# Radii.net
KiCad netlist of a schematic drawn in EAGLE
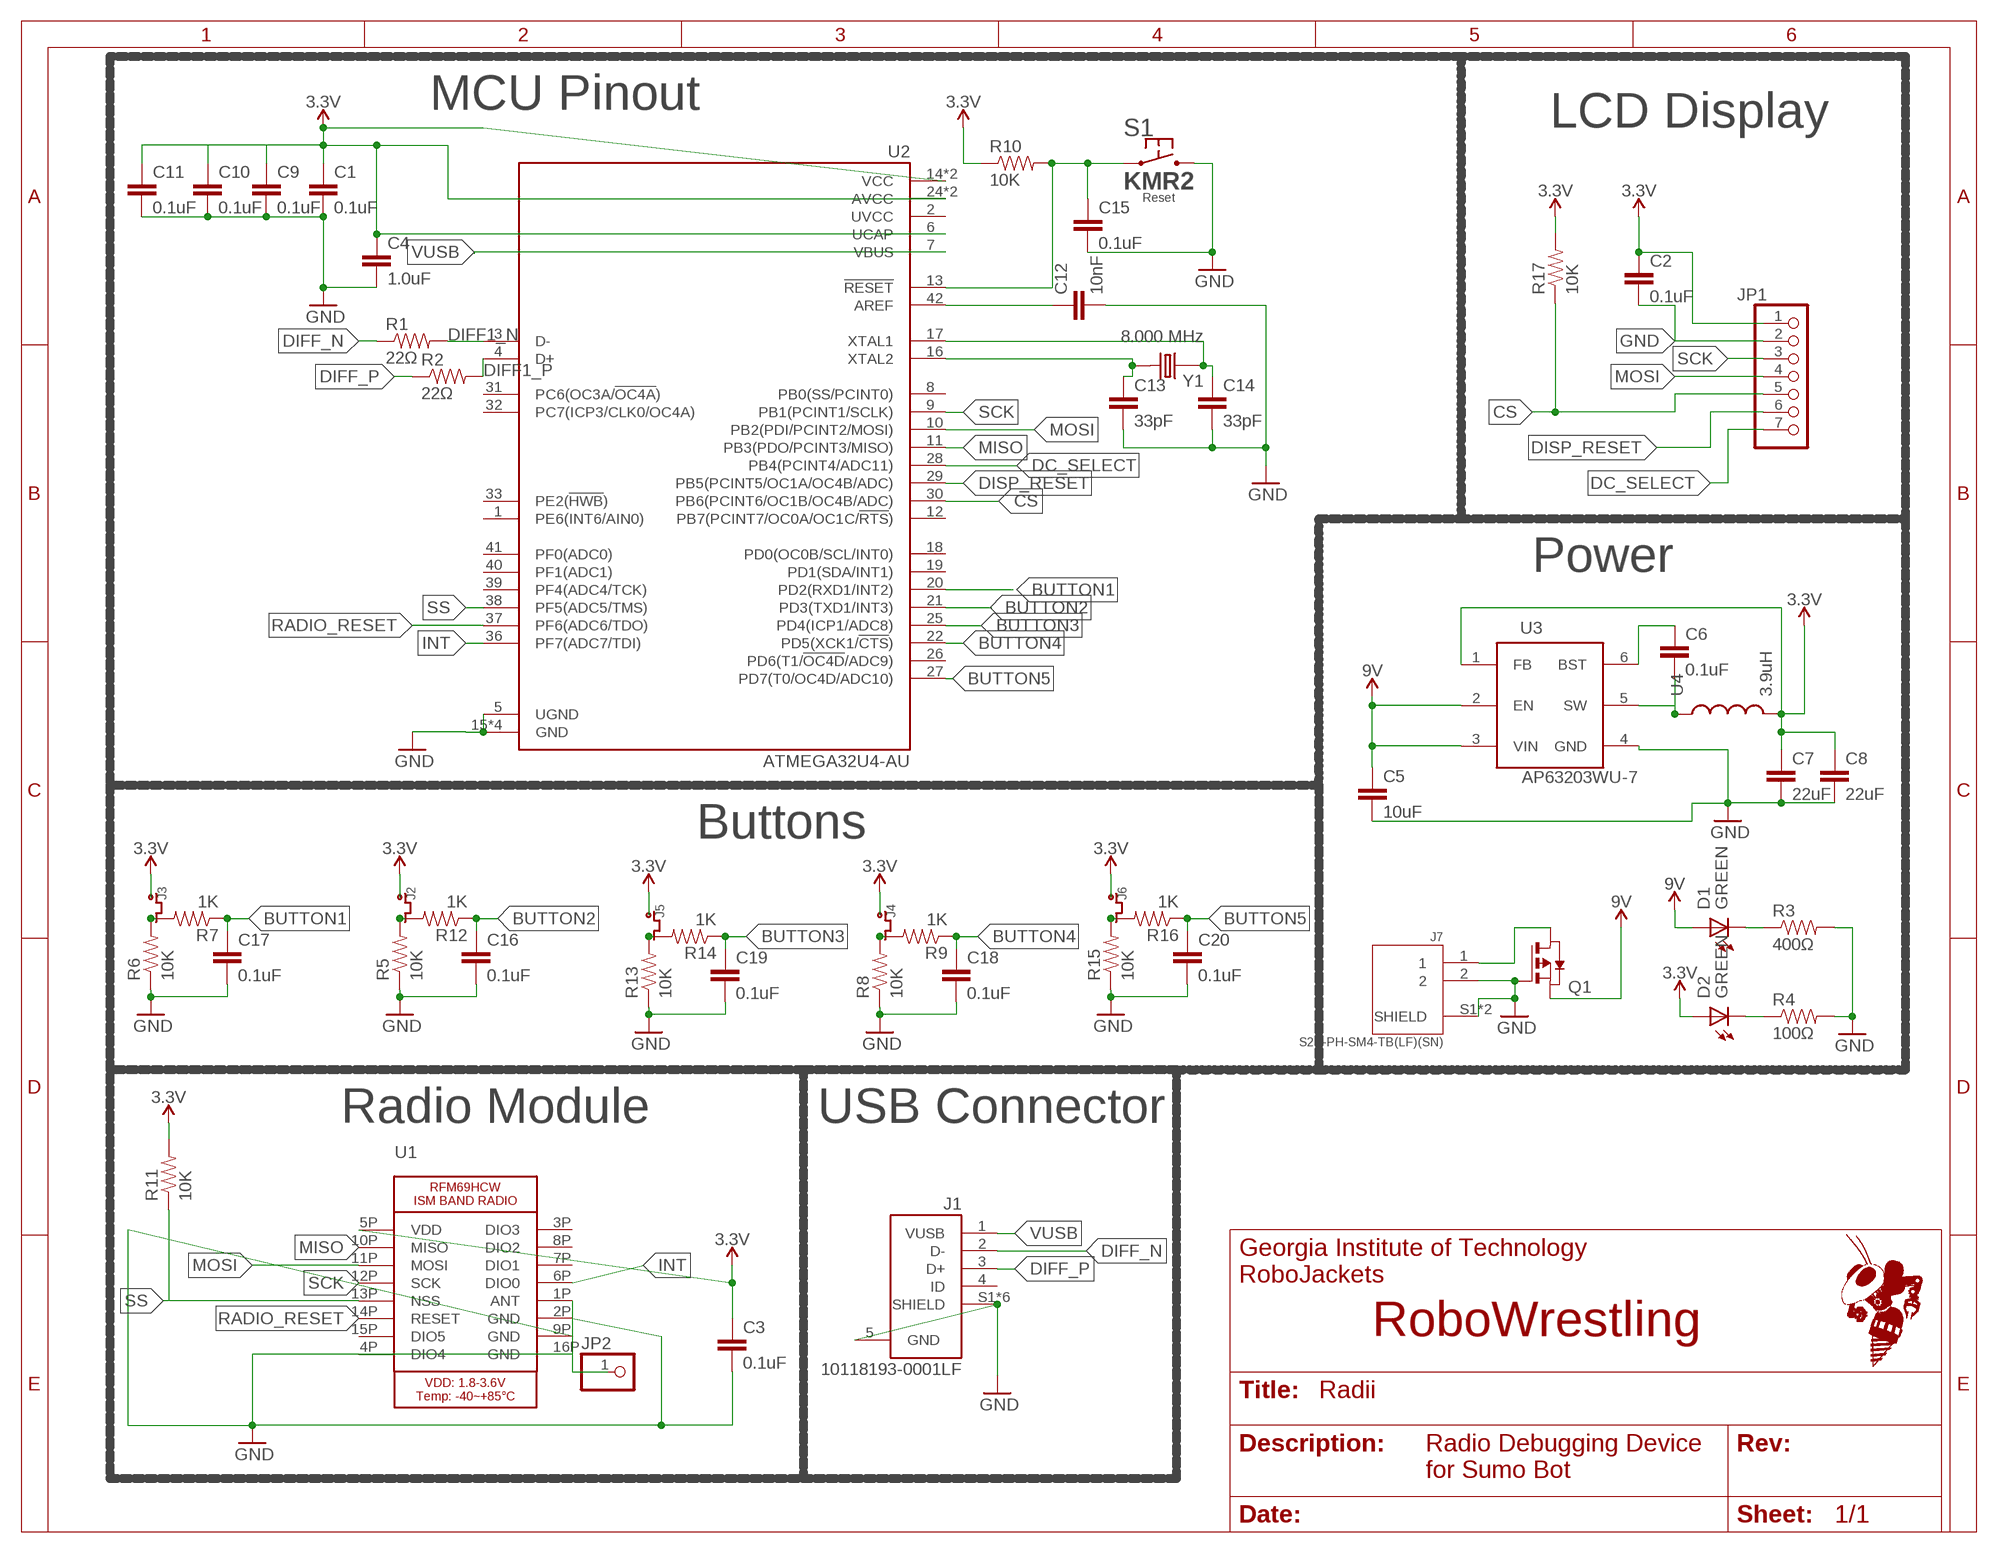
[diagram p0: schematic, sheet 1]

(export (version "E")
  (design (tool "Eeschema 10.0.6"))
  (components
    (comp (ref "C1")
      (value "0.1uF")
      (footprint "eagle-import:0603")
      (libsource (lib "eagle-import") (part "0.1UF-0603-25V-(+80/-20%)"))
    )
    (comp (ref "C2")
      (value "0.1uF")
      (footprint "eagle-import:0603")
      (libsource (lib "eagle-import") (part "0.1UF-0603-25V-(+80/-20%)"))
    )
    (comp (ref "C3")
      (value "0.1uF")
      (footprint "eagle-import:0603")
      (libsource (lib "eagle-import") (part "0.1UF-0603-25V-(+80/-20%)"))
    )
    (comp (ref "C4")
      (value "1.0uF")
      (footprint "eagle-import:0603")
      (libsource (lib "eagle-import") (part "1.0UF-0603-16V-10%"))
    )
    (comp (ref "C5")
      (value "10uF")
      (footprint "eagle-import:0603")
      (libsource (lib "eagle-import") (part "10UF-0603-6.3V-20%"))
    )
    (comp (ref "C6")
      (value "0.1uF")
      (footprint "eagle-import:0603")
      (libsource (lib "eagle-import") (part "0.1UF-0603-25V-(+80/-20%)"))
    )
    (comp (ref "C7")
      (value "22uF")
      (footprint "eagle-import:1210")
      (libsource (lib "eagle-import") (part "22UF-1210-16V-20%"))
    )
    (comp (ref "C8")
      (value "22uF")
      (footprint "eagle-import:1210")
      (libsource (lib "eagle-import") (part "22UF-1210-16V-20%"))
    )
    (comp (ref "C9")
      (value "0.1uF")
      (footprint "eagle-import:0603")
      (libsource (lib "eagle-import") (part "0.1UF-0603-25V-(+80/-20%)"))
    )
    (comp (ref "C10")
      (value "0.1uF")
      (footprint "eagle-import:0603")
      (libsource (lib "eagle-import") (part "0.1UF-0603-25V-(+80/-20%)"))
    )
    (comp (ref "C11")
      (value "0.1uF")
      (footprint "eagle-import:0603")
      (libsource (lib "eagle-import") (part "0.1UF-0603-25V-(+80/-20%)"))
    )
    (comp (ref "C12")
      (value "10nF")
      (footprint "eagle-import:0603")
      (libsource (lib "eagle-import") (part "10NF-0603-50V-10%"))
    )
    (comp (ref "C13")
      (value "33pF")
      (footprint "eagle-import:0603")
      (libsource (lib "eagle-import") (part "33PF-0603-50V-5%"))
    )
    (comp (ref "C14")
      (value "33pF")
      (footprint "eagle-import:0603")
      (libsource (lib "eagle-import") (part "33PF-0603-50V-5%"))
    )
    (comp (ref "C15")
      (value "0.1uF")
      (footprint "eagle-import:0603")
      (libsource (lib "eagle-import") (part "0.1UF-0603-25V-(+80/-20%)"))
    )
    (comp (ref "C16")
      (value "0.1uF")
      (footprint "eagle-import:0603")
      (libsource (lib "eagle-import") (part "0.1UF-0603-25V-(+80/-20%)"))
    )
    (comp (ref "C17")
      (value "0.1uF")
      (footprint "eagle-import:0603")
      (libsource (lib "eagle-import") (part "0.1UF-0603-25V-(+80/-20%)"))
    )
    (comp (ref "C18")
      (value "0.1uF")
      (footprint "eagle-import:0603")
      (libsource (lib "eagle-import") (part "0.1UF-0603-25V-(+80/-20%)"))
    )
    (comp (ref "C19")
      (value "0.1uF")
      (footprint "eagle-import:0603")
      (libsource (lib "eagle-import") (part "0.1UF-0603-25V-(+80/-20%)"))
    )
    (comp (ref "C20")
      (value "0.1uF")
      (footprint "eagle-import:0603")
      (libsource (lib "eagle-import") (part "0.1UF-0603-25V-(+80/-20%)"))
    )
    (comp (ref "D1")
      (value "GREEN")
      (footprint "eagle-import:CHIP-LED0603")
      (libsource (lib "eagle-import") (part "LED-SMD"))
    )
    (comp (ref "D2")
      (value "GREEN")
      (footprint "eagle-import:CHIP-LED0603")
      (libsource (lib "eagle-import") (part "LED-SMD"))
    )
    (comp (ref "J1")
      (value "10118193-0001LF")
      (footprint "eagle-import:FCI_10118193-0001LF")
      (libsource (lib "eagle-import") (part "10118193-0001LF"))
    )
    (comp (ref "J2")
      (value "BUTTON")
      (footprint "eagle-import:1X02")
      (libsource (lib "eagle-import") (part "BUTTON"))
    )
    (comp (ref "J3")
      (value "BUTTON")
      (footprint "eagle-import:1X02")
      (libsource (lib "eagle-import") (part "BUTTON"))
    )
    (comp (ref "J4")
      (value "BUTTON")
      (footprint "eagle-import:1X02")
      (libsource (lib "eagle-import") (part "BUTTON"))
    )
    (comp (ref "J5")
      (value "BUTTON")
      (footprint "eagle-import:1X02")
      (libsource (lib "eagle-import") (part "BUTTON"))
    )
    (comp (ref "J6")
      (value "BUTTON")
      (footprint "eagle-import:1X02")
      (libsource (lib "eagle-import") (part "BUTTON"))
    )
    (comp (ref "J7")
      (value "S2B-PH-SM4-TB(LF)(SN)")
      (footprint "eagle-import:JST_S2B-PH-SM4-TB(LF)(SN)")
      (fields (field (name "DIGI-KEY_PART_NUMBER") "455-1749-1-ND"))
      (libsource (lib "eagle-import") (part "S2B-PH-SM4-TB(LF)(SN)"))
    )
    (comp (ref "JP1")
      (value "PINHD-1X7")
      (footprint "eagle-import:1X07")
      (libsource (lib "eagle-import") (part "PINHD-1X7"))
    )
    (comp (ref "JP2")
      (value "PINHD-1X1")
      (footprint "eagle-import:1X01")
      (libsource (lib "eagle-import") (part "PINHD-1X1"))
    )
    (comp (ref "Q1")
      (value "PMOS")
      (footprint "eagle-import:SOT-23-3")
      (libsource (lib "eagle-import") (part "PMOS"))
    )
    (comp (ref "R1")
      (value "22Ω")
      (footprint "eagle-import:0603-RES")
      (libsource (lib "eagle-import") (part "22OHM1/10W1%(0603)"))
    )
    (comp (ref "R2")
      (value "22Ω")
      (footprint "eagle-import:0603-RES")
      (libsource (lib "eagle-import") (part "22OHM1/10W1%(0603)"))
    )
    (comp (ref "R3")
      (value "400Ω")
      (footprint "eagle-import:0603-RES")
      (libsource (lib "eagle-import") (part "RESISTOR0603"))
    )
    (comp (ref "R4")
      (value "100Ω")
      (footprint "eagle-import:0603-RES")
      (libsource (lib "eagle-import") (part "RESISTOR0603"))
    )
    (comp (ref "R5")
      (value "10K")
      (footprint "eagle-import:0603-RES")
      (libsource (lib "eagle-import") (part "10KOHM-1/10W-1%(0603)0603"))
    )
    (comp (ref "R6")
      (value "10K")
      (footprint "eagle-import:0603-RES")
      (libsource (lib "eagle-import") (part "10KOHM-1/10W-1%(0603)0603"))
    )
    (comp (ref "R7")
      (value "1K")
      (footprint "eagle-import:0603-RES")
      (libsource (lib "eagle-import") (part "10KOHM-1/10W-1%(0603)0603"))
    )
    (comp (ref "R8")
      (value "10K")
      (footprint "eagle-import:0603-RES")
      (libsource (lib "eagle-import") (part "10KOHM-1/10W-1%(0603)0603"))
    )
    (comp (ref "R9")
      (value "1K")
      (footprint "eagle-import:0603-RES")
      (libsource (lib "eagle-import") (part "10KOHM-1/10W-1%(0603)0603"))
    )
    (comp (ref "R10")
      (value "10K")
      (footprint "eagle-import:0603-RES")
      (libsource (lib "eagle-import") (part "10KOHM-1/10W-1%(0603)0603"))
    )
    (comp (ref "R11")
      (value "10K")
      (footprint "eagle-import:0603-RES")
      (libsource (lib "eagle-import") (part "10KOHM-1/10W-1%(0603)0603"))
    )
    (comp (ref "R12")
      (value "1K")
      (footprint "eagle-import:0603-RES")
      (libsource (lib "eagle-import") (part "10KOHM-1/10W-1%(0603)0603"))
    )
    (comp (ref "R13")
      (value "10K")
      (footprint "eagle-import:0603-RES")
      (libsource (lib "eagle-import") (part "10KOHM-1/10W-1%(0603)0603"))
    )
    (comp (ref "R14")
      (value "1K")
      (footprint "eagle-import:0603-RES")
      (libsource (lib "eagle-import") (part "10KOHM-1/10W-1%(0603)0603"))
    )
    (comp (ref "R15")
      (value "10K")
      (footprint "eagle-import:0603-RES")
      (libsource (lib "eagle-import") (part "10KOHM-1/10W-1%(0603)0603"))
    )
    (comp (ref "R16")
      (value "1K")
      (footprint "eagle-import:0603-RES")
      (libsource (lib "eagle-import") (part "10KOHM-1/10W-1%(0603)0603"))
    )
    (comp (ref "R17")
      (value "10K")
      (footprint "eagle-import:0603-RES")
      (libsource (lib "eagle-import") (part "10KOHM-1/10W-1%(0603)0603"))
    )
    (comp (ref "S1")
      (value "KMR2")
      (footprint "eagle-import:KMR2")
      (fields (field (name "FUNCTION") "Reset"))
      (libsource (lib "eagle-import") (part "KMR2"))
    )
    (comp (ref "U1")
      (value "RFM69HCW_SMT")
      (footprint "eagle-import:RFMHCW_SMT")
      (libsource (lib "eagle-import") (part "RFM69HCW_SMT"))
    )
    (comp (ref "U2")
      (value "ATMEGA32U4-AU")
      (footprint "eagle-import:44-TQFP(10X10)")
      (libsource (lib "eagle-import") (part "ATMEGA32U4-AUR"))
    )
    (comp (ref "U3")
      (value "AP63203WU-7")
      (footprint "eagle-import:TSOT-23-6")
      (libsource (lib "eagle-import") (part "AP63203WU-7"))
    )
    (comp (ref "U4")
      (value "3.9uH")
      (footprint "eagle-import:1255AY-3R9N=P3")
      (fields (field (name "TOLERANCE") "±30%"))
      (libsource (lib "eagle-import") (part "1255AY-3R9N=P3"))
    )
    (comp (ref "Y1")
      (value "8.000 MHz")
      (footprint "eagle-import:XTAL_ECS-80-20-5PX-TR")
      (libsource (lib "eagle-import") (part "ECS-80-20-5PX-TR"))
    )
  )
  (nets
    (net (code "1") (name "/DIFF1_N") (class "Default")
      (node (ref "R1") (pin "2") (pinfunction "2_2") (pintype "passive"))
      (node (ref "U2") (pin "3") (pinfunction "D-_3") (pintype "passive"))
    )
    (net (code "2") (name "/DIFF1_P") (class "Default")
      (node (ref "R2") (pin "2") (pinfunction "2_2") (pintype "passive"))
      (node (ref "U2") (pin "4") (pinfunction "D+_4") (pintype "passive"))
    )
    (net (code "3") (name "3.3V") (class "Default")
      (node (ref "C1") (pin "1") (pinfunction "1_1") (pintype "passive"))
      (node (ref "C10") (pin "1") (pinfunction "1_1") (pintype "passive"))
      (node (ref "C11") (pin "1") (pinfunction "1_1") (pintype "passive"))
      (node (ref "C2") (pin "1") (pinfunction "1_1") (pintype "passive"))
      (node (ref "C3") (pin "1") (pinfunction "1_1") (pintype "passive"))
      (node (ref "C4") (pin "1") (pinfunction "1_1") (pintype "passive"))
      (node (ref "C7") (pin "1") (pinfunction "1_1") (pintype "passive"))
      (node (ref "C8") (pin "1") (pinfunction "1_1") (pintype "passive"))
      (node (ref "C9") (pin "1") (pinfunction "1_1") (pintype "passive"))
      (node (ref "D2") (pin "A") (pinfunction "A_A") (pintype "passive"))
      (node (ref "J2") (pin "1") (pinfunction "P$1_1") (pintype "passive"))
      (node (ref "J3") (pin "1") (pinfunction "P$1_1") (pintype "passive"))
      (node (ref "J4") (pin "1") (pinfunction "P$1_1") (pintype "passive"))
      (node (ref "J5") (pin "1") (pinfunction "P$1_1") (pintype "passive"))
      (node (ref "J6") (pin "1") (pinfunction "P$1_1") (pintype "passive"))
      (node (ref "JP1") (pin "1") (pinfunction "1_1") (pintype "passive"))
      (node (ref "R10") (pin "1") (pinfunction "1_1") (pintype "passive"))
      (node (ref "R11") (pin "2") (pinfunction "2_2") (pintype "passive"))
      (node (ref "R17") (pin "2") (pinfunction "2_2") (pintype "passive"))
      (node (ref "U1") (pin "5P") (pinfunction "VDD_5P") (pintype "passive"))
      (node (ref "U2") (pin "14") (pinfunction "VCC_14") (pintype "passive"))
      (node (ref "U2") (pin "24") (pinfunction "AVCC_24") (pintype "passive"))
      (node (ref "U2") (pin "34") (pinfunction "VCC_34") (pintype "passive"))
      (node (ref "U2") (pin "44") (pinfunction "AVCC_44") (pintype "passive"))
      (node (ref "U2") (pin "6") (pinfunction "UCAP_6") (pintype "passive"))
      (node (ref "U3") (pin "1") (pinfunction "FB_1") (pintype "passive"))
      (node (ref "U4") (pin "2") (pinfunction "2_2") (pintype "passive"))
    )
    (net (code "4") (name "9V") (class "Default")
      (node (ref "C5") (pin "1") (pinfunction "1_1") (pintype "passive"))
      (node (ref "D1") (pin "A") (pinfunction "A_A") (pintype "passive"))
      (node (ref "Q1") (pin "2") (pinfunction "S_2") (pintype "passive"))
      (node (ref "U3") (pin "2") (pinfunction "EN_2") (pintype "passive"))
      (node (ref "U3") (pin "3") (pinfunction "VIN_3") (pintype "passive"))
    )
    (net (code "5") (name "BUTTON1") (class "Default")
      (node (ref "C17") (pin "1") (pinfunction "1_1") (pintype "passive"))
      (node (ref "R7") (pin "1") (pinfunction "1_1") (pintype "passive"))
      (node (ref "U2") (pin "20") (pinfunction "PD2(RXD1/INT2)_20") (pintype "passive"))
    )
    (net (code "6") (name "BUTTON2") (class "Default")
      (node (ref "C16") (pin "1") (pinfunction "1_1") (pintype "passive"))
      (node (ref "R12") (pin "1") (pinfunction "1_1") (pintype "passive"))
      (node (ref "U2") (pin "21") (pinfunction "PD3(TXD1/INT3)_21") (pintype "passive"))
    )
    (net (code "7") (name "BUTTON3") (class "Default")
      (node (ref "C19") (pin "1") (pinfunction "1_1") (pintype "passive"))
      (node (ref "R14") (pin "1") (pinfunction "1_1") (pintype "passive"))
      (node (ref "U2") (pin "25") (pinfunction "PD4(ICP1/ADC8)_25") (pintype "passive"))
    )
    (net (code "8") (name "BUTTON4") (class "Default")
      (node (ref "C18") (pin "1") (pinfunction "1_1") (pintype "passive"))
      (node (ref "R9") (pin "1") (pinfunction "1_1") (pintype "passive"))
      (node (ref "U2") (pin "22") (pinfunction "PD5(XCK1/~{CTS})_22") (pintype "passive"))
    )
    (net (code "9") (name "BUTTON5") (class "Default")
      (node (ref "C20") (pin "1") (pinfunction "1_1") (pintype "passive"))
      (node (ref "R16") (pin "1") (pinfunction "1_1") (pintype "passive"))
      (node (ref "U2") (pin "27") (pinfunction "PD7(T0/OC4D/ADC10)_27") (pintype "passive"))
    )
    (net (code "10") (name "CS") (class "Default")
      (node (ref "JP1") (pin "5") (pinfunction "5_5") (pintype "passive"))
      (node (ref "R17") (pin "1") (pinfunction "1_1") (pintype "passive"))
      (node (ref "U2") (pin "30") (pinfunction "PB6(PCINT6/OC1B/OC4B/ADC)_30") (pintype "passive"))
    )
    (net (code "11") (name "DC_SELECT") (class "Default")
      (node (ref "JP1") (pin "7") (pinfunction "7_7") (pintype "passive"))
      (node (ref "U2") (pin "28") (pinfunction "PB4(PCINT4/ADC11)_28") (pintype "passive"))
    )
    (net (code "12") (name "DIFF_N") (class "Default")
      (node (ref "J1") (pin "2") (pinfunction "D-_2") (pintype "passive"))
      (node (ref "R1") (pin "1") (pinfunction "1_1") (pintype "passive"))
    )
    (net (code "13") (name "DIFF_P") (class "Default")
      (node (ref "J1") (pin "3") (pinfunction "D+_3") (pintype "passive"))
      (node (ref "R2") (pin "1") (pinfunction "1_1") (pintype "passive"))
    )
    (net (code "14") (name "DISP_RESET") (class "Default")
      (node (ref "JP1") (pin "6") (pinfunction "6_6") (pintype "passive"))
      (node (ref "U2") (pin "29") (pinfunction "PB5(PCINT5/OC1A/OC4B/ADC)_29") (pintype "passive"))
    )
    (net (code "15") (name "GND") (class "Default")
      (node (ref "C1") (pin "2") (pinfunction "2_2") (pintype "passive"))
      (node (ref "C10") (pin "2") (pinfunction "2_2") (pintype "passive"))
      (node (ref "C11") (pin "2") (pinfunction "2_2") (pintype "passive"))
      (node (ref "C12") (pin "2") (pinfunction "2_2") (pintype "passive"))
      (node (ref "C13") (pin "2") (pinfunction "2_2") (pintype "passive"))
      (node (ref "C14") (pin "2") (pinfunction "2_2") (pintype "passive"))
      (node (ref "C15") (pin "2") (pinfunction "2_2") (pintype "passive"))
      (node (ref "C16") (pin "2") (pinfunction "2_2") (pintype "passive"))
      (node (ref "C17") (pin "2") (pinfunction "2_2") (pintype "passive"))
      (node (ref "C18") (pin "2") (pinfunction "2_2") (pintype "passive"))
      (node (ref "C19") (pin "2") (pinfunction "2_2") (pintype "passive"))
      (node (ref "C2") (pin "2") (pinfunction "2_2") (pintype "passive"))
      (node (ref "C20") (pin "2") (pinfunction "2_2") (pintype "passive"))
      (node (ref "C3") (pin "2") (pinfunction "2_2") (pintype "passive"))
      (node (ref "C4") (pin "2") (pinfunction "2_2") (pintype "passive"))
      (node (ref "C5") (pin "2") (pinfunction "2_2") (pintype "passive"))
      (node (ref "C7") (pin "2") (pinfunction "2_2") (pintype "passive"))
      (node (ref "C8") (pin "2") (pinfunction "2_2") (pintype "passive"))
      (node (ref "C9") (pin "2") (pinfunction "2_2") (pintype "passive"))
      (node (ref "J1") (pin "5") (pinfunction "GND_5") (pintype "passive"))
      (node (ref "J1") (pin "S1") (pinfunction "SHIELD_S1") (pintype "passive"))
      (node (ref "J1") (pin "S2") (pinfunction "SHIELD_S2") (pintype "passive"))
      (node (ref "J1") (pin "S3") (pinfunction "SHIELD_S3") (pintype "passive"))
      (node (ref "J1") (pin "S4") (pinfunction "SHIELD_S4") (pintype "passive"))
      (node (ref "J1") (pin "S5") (pinfunction "SHIELD_S5") (pintype "passive"))
      (node (ref "J1") (pin "S6") (pinfunction "SHIELD_S6") (pintype "passive"))
      (node (ref "J7") (pin "2") (pinfunction "2_2") (pintype "passive"))
      (node (ref "J7") (pin "S1") (pinfunction "SHIELD_S1") (pintype "passive"))
      (node (ref "J7") (pin "S2") (pinfunction "SHIELD_S2") (pintype "passive"))
      (node (ref "JP1") (pin "2") (pinfunction "2_2") (pintype "passive"))
      (node (ref "Q1") (pin "1") (pinfunction "G_1") (pintype "passive"))
      (node (ref "R13") (pin "1") (pinfunction "1_1") (pintype "passive"))
      (node (ref "R15") (pin "1") (pinfunction "1_1") (pintype "passive"))
      (node (ref "R3") (pin "2") (pinfunction "2_2") (pintype "passive"))
      (node (ref "R4") (pin "2") (pinfunction "2_2") (pintype "passive"))
      (node (ref "R5") (pin "1") (pinfunction "1_1") (pintype "passive"))
      (node (ref "R6") (pin "1") (pinfunction "1_1") (pintype "passive"))
      (node (ref "R8") (pin "1") (pinfunction "1_1") (pintype "passive"))
      (node (ref "S1") (pin "2.1") (pinfunction "2_2.1") (pintype "passive"))
      (node (ref "S1") (pin "2.2") (pinfunction "2_2.2") (pintype "passive"))
      (node (ref "U1") (pin "16P") (pinfunction "GND_16P") (pintype "passive"))
      (node (ref "U1") (pin "2P") (pinfunction "GND_2P") (pintype "passive"))
      (node (ref "U1") (pin "9P") (pinfunction "GND_9P") (pintype "passive"))
      (node (ref "U2") (pin "15") (pinfunction "GND_15") (pintype "passive"))
      (node (ref "U2") (pin "23") (pinfunction "GND_23") (pintype "passive"))
      (node (ref "U2") (pin "35") (pinfunction "GND_35") (pintype "passive"))
      (node (ref "U2") (pin "43") (pinfunction "GND_43") (pintype "passive"))
      (node (ref "U2") (pin "5") (pinfunction "UGND_5") (pintype "passive"))
      (node (ref "U3") (pin "4") (pinfunction "GND_4") (pintype "passive"))
    )
    (net (code "16") (name "INT") (class "Default")
      (node (ref "U1") (pin "6P") (pinfunction "DIO0_6P") (pintype "passive"))
      (node (ref "U2") (pin "36") (pinfunction "PF7(ADC7/TDI)_36") (pintype "passive"))
    )
    (net (code "17") (name "MISO") (class "Default")
      (node (ref "U1") (pin "10P") (pinfunction "MISO_10P") (pintype "passive"))
      (node (ref "U2") (pin "11") (pinfunction "PB3(PDO/PCINT3/MISO)_11") (pintype "passive"))
    )
    (net (code "18") (name "MOSI") (class "Default")
      (node (ref "JP1") (pin "4") (pinfunction "4_4") (pintype "passive"))
      (node (ref "U1") (pin "11P") (pinfunction "MOSI_11P") (pintype "passive"))
      (node (ref "U2") (pin "10") (pinfunction "PB2(PDI/PCINT2/MOSI)_10") (pintype "passive"))
    )
    (net (code "19") (name "Net-(D1-K)") (class "Default")
      (node (ref "D1") (pin "C") (pinfunction "K_C") (pintype "passive"))
      (node (ref "R3") (pin "1") (pinfunction "1_1") (pintype "passive"))
    )
    (net (code "20") (name "Net-(D2-K)") (class "Default")
      (node (ref "D2") (pin "C") (pinfunction "K_C") (pintype "passive"))
      (node (ref "R4") (pin "1") (pinfunction "1_1") (pintype "passive"))
    )
    (net (code "21") (name "Net-(J2-P$2)") (class "Default")
      (node (ref "J2") (pin "2") (pinfunction "P$2_2") (pintype "passive"))
      (node (ref "R12") (pin "2") (pinfunction "2_2") (pintype "passive"))
      (node (ref "R5") (pin "2") (pinfunction "2_2") (pintype "passive"))
    )
    (net (code "22") (name "Net-(J3-P$2)") (class "Default")
      (node (ref "J3") (pin "2") (pinfunction "P$2_2") (pintype "passive"))
      (node (ref "R6") (pin "2") (pinfunction "2_2") (pintype "passive"))
      (node (ref "R7") (pin "2") (pinfunction "2_2") (pintype "passive"))
    )
    (net (code "23") (name "Net-(J4-P$2)") (class "Default")
      (node (ref "J4") (pin "2") (pinfunction "P$2_2") (pintype "passive"))
      (node (ref "R8") (pin "2") (pinfunction "2_2") (pintype "passive"))
      (node (ref "R9") (pin "2") (pinfunction "2_2") (pintype "passive"))
    )
    (net (code "24") (name "Net-(J5-P$2)") (class "Default")
      (node (ref "J5") (pin "2") (pinfunction "P$2_2") (pintype "passive"))
      (node (ref "R13") (pin "2") (pinfunction "2_2") (pintype "passive"))
      (node (ref "R14") (pin "2") (pinfunction "2_2") (pintype "passive"))
    )
    (net (code "25") (name "Net-(J6-P$2)") (class "Default")
      (node (ref "J6") (pin "2") (pinfunction "P$2_2") (pintype "passive"))
      (node (ref "R15") (pin "2") (pinfunction "2_2") (pintype "passive"))
      (node (ref "R16") (pin "2") (pinfunction "2_2") (pintype "passive"))
    )
    (net (code "26") (name "Net-(Q1-D)") (class "Default")
      (node (ref "J7") (pin "1") (pinfunction "1_1") (pintype "passive"))
      (node (ref "Q1") (pin "3") (pinfunction "D_3") (pintype "passive"))
    )
    (net (code "27") (name "Net-(U1-ANT)") (class "Default")
      (node (ref "JP2") (pin "1") (pinfunction "1_1") (pintype "passive"))
      (node (ref "U1") (pin "1P") (pinfunction "ANT_1P") (pintype "passive"))
    )
    (net (code "28") (name "Net-(U2-AREF)") (class "Default")
      (node (ref "C12") (pin "1") (pinfunction "1_1") (pintype "passive"))
      (node (ref "U2") (pin "42") (pinfunction "AREF_42") (pintype "passive"))
    )
    (net (code "29") (name "Net-(U2-XTAL1)") (class "Default")
      (node (ref "C14") (pin "1") (pinfunction "1_1") (pintype "passive"))
      (node (ref "U2") (pin "17") (pinfunction "XTAL1_17") (pintype "passive"))
      (node (ref "Y1") (pin "1") (pinfunction "1_1") (pintype "passive"))
    )
    (net (code "30") (name "Net-(U2-XTAL2)") (class "Default")
      (node (ref "C13") (pin "1") (pinfunction "1_1") (pintype "passive"))
      (node (ref "U2") (pin "16") (pinfunction "XTAL2_16") (pintype "passive"))
      (node (ref "Y1") (pin "2") (pinfunction "2_2") (pintype "passive"))
    )
    (net (code "31") (name "Net-(U2-~{RESET})") (class "Default")
      (node (ref "C15") (pin "1") (pinfunction "1_1") (pintype "passive"))
      (node (ref "R10") (pin "2") (pinfunction "2_2") (pintype "passive"))
      (node (ref "S1") (pin "1.1") (pinfunction "1_1.1") (pintype "passive"))
      (node (ref "S1") (pin "1.2") (pinfunction "1_1.2") (pintype "passive"))
      (node (ref "U2") (pin "13") (pinfunction "~{RESET}_13") (pintype "passive"))
    )
    (net (code "32") (name "Net-(U3-BST)") (class "Default")
      (node (ref "C6") (pin "1") (pinfunction "1_1") (pintype "passive"))
      (node (ref "U3") (pin "6") (pinfunction "BST_6") (pintype "passive"))
    )
    (net (code "33") (name "Net-(U3-SW)") (class "Default")
      (node (ref "C6") (pin "2") (pinfunction "2_2") (pintype "passive"))
      (node (ref "U3") (pin "5") (pinfunction "SW_5") (pintype "passive"))
      (node (ref "U4") (pin "1") (pinfunction "1_1") (pintype "passive"))
    )
    (net (code "34") (name "RADIO_RESET") (class "Default")
      (node (ref "U1") (pin "14P") (pinfunction "RESET_14P") (pintype "passive"))
      (node (ref "U2") (pin "37") (pinfunction "PF6(ADC6/TDO)_37") (pintype "passive"))
    )
    (net (code "35") (name "SCK") (class "Default")
      (node (ref "JP1") (pin "3") (pinfunction "3_3") (pintype "passive"))
      (node (ref "U1") (pin "12P") (pinfunction "SCK_12P") (pintype "passive"))
      (node (ref "U2") (pin "9") (pinfunction "PB1(PCINT1/SCLK)_9") (pintype "passive"))
    )
    (net (code "36") (name "SS") (class "Default")
      (node (ref "R11") (pin "1") (pinfunction "1_1") (pintype "passive"))
      (node (ref "U1") (pin "13P") (pinfunction "NSS_13P") (pintype "passive"))
      (node (ref "U2") (pin "38") (pinfunction "PF5(ADC5/TMS)_38") (pintype "passive"))
    )
    (net (code "37") (name "VUSB") (class "Default")
      (node (ref "J1") (pin "1") (pinfunction "VUSB_1") (pintype "passive"))
      (node (ref "U2") (pin "7") (pinfunction "VBUS_7") (pintype "passive"))
    )
    (net (code "38") (name "unconnected-(J1-ID-Pad4)") (class "Default")
      (node (ref "J1") (pin "4") (pinfunction "ID_4") (pintype "passive"))
    )
    (net (code "39") (name "unconnected-(U1-DIO1-Pad7P)") (class "Default")
      (node (ref "U1") (pin "7P") (pinfunction "DIO1_7P") (pintype "passive"))
    )
    (net (code "40") (name "unconnected-(U1-DIO2-Pad8P)") (class "Default")
      (node (ref "U1") (pin "8P") (pinfunction "DIO2_8P") (pintype "passive"))
    )
    (net (code "41") (name "unconnected-(U1-DIO3-Pad3P)") (class "Default")
      (node (ref "U1") (pin "3P") (pinfunction "DIO3_3P") (pintype "passive"))
    )
    (net (code "42") (name "unconnected-(U1-DIO4-Pad4P)") (class "Default")
      (node (ref "U1") (pin "4P") (pinfunction "DIO4_4P") (pintype "passive"))
    )
    (net (code "43") (name "unconnected-(U1-DIO5-Pad15P)") (class "Default")
      (node (ref "U1") (pin "15P") (pinfunction "DIO5_15P") (pintype "passive"))
    )
    (net (code "44") (name "unconnected-(U2-PB0(SS{slash}PCINT0)-Pad8)") (class "Default")
      (node (ref "U2") (pin "8") (pinfunction "PB0(SS/PCINT0)_8") (pintype "passive"))
    )
    (net (code "45") (name "unconnected-(U2-PB7(PCINT7{slash}OC0A{slash}OC1C{slash}~{RTS})-Pad12)") (class "Default")
      (node (ref "U2") (pin "12") (pinfunction "PB7(PCINT7/OC0A/OC1C/~{RTS})_12") (pintype "passive"))
    )
    (net (code "46") (name "unconnected-(U2-PC6(OC3A{slash}~{OC4A})-Pad31)") (class "Default")
      (node (ref "U2") (pin "31") (pinfunction "PC6(OC3A/~{OC4A})_31") (pintype "passive"))
    )
    (net (code "47") (name "unconnected-(U2-PC7(ICP3{slash}CLK0{slash}OC4A)-Pad32)") (class "Default")
      (node (ref "U2") (pin "32") (pinfunction "PC7(ICP3/CLK0/OC4A)_32") (pintype "passive"))
    )
    (net (code "48") (name "unconnected-(U2-PD0(OC0B{slash}SCL{slash}INT0)-Pad18)") (class "Default")
      (node (ref "U2") (pin "18") (pinfunction "PD0(OC0B/SCL/INT0)_18") (pintype "passive"))
    )
    (net (code "49") (name "unconnected-(U2-PD1(SDA{slash}INT1)-Pad19)") (class "Default")
      (node (ref "U2") (pin "19") (pinfunction "PD1(SDA/INT1)_19") (pintype "passive"))
    )
    (net (code "50") (name "unconnected-(U2-PD6(T1{slash}~{OC4D}{slash}ADC9)-Pad26)") (class "Default")
      (node (ref "U2") (pin "26") (pinfunction "PD6(T1/~{OC4D}/ADC9)_26") (pintype "passive"))
    )
    (net (code "51") (name "unconnected-(U2-PE2(~{HWB})-Pad33)") (class "Default")
      (node (ref "U2") (pin "33") (pinfunction "PE2(~{HWB})_33") (pintype "passive"))
    )
    (net (code "52") (name "unconnected-(U2-PE6(INT6{slash}AIN0)-Pad1)") (class "Default")
      (node (ref "U2") (pin "1") (pinfunction "PE6(INT6/AIN0)_1") (pintype "passive"))
    )
    (net (code "53") (name "unconnected-(U2-PF0(ADC0)-Pad41)") (class "Default")
      (node (ref "U2") (pin "41") (pinfunction "PF0(ADC0)_41") (pintype "passive"))
    )
    (net (code "54") (name "unconnected-(U2-PF1(ADC1)-Pad40)") (class "Default")
      (node (ref "U2") (pin "40") (pinfunction "PF1(ADC1)_40") (pintype "passive"))
    )
    (net (code "55") (name "unconnected-(U2-PF4(ADC4{slash}TCK)-Pad39)") (class "Default")
      (node (ref "U2") (pin "39") (pinfunction "PF4(ADC4/TCK)_39") (pintype "passive"))
    )
    (net (code "56") (name "unconnected-(U2-UVCC-Pad2)") (class "Default")
      (node (ref "U2") (pin "2") (pinfunction "UVCC_2") (pintype "passive"))
    )
  )
)
